# DC-DC_Converter_Module_V1_1.net
KiCad netlist of a schematic drawn in EAGLE
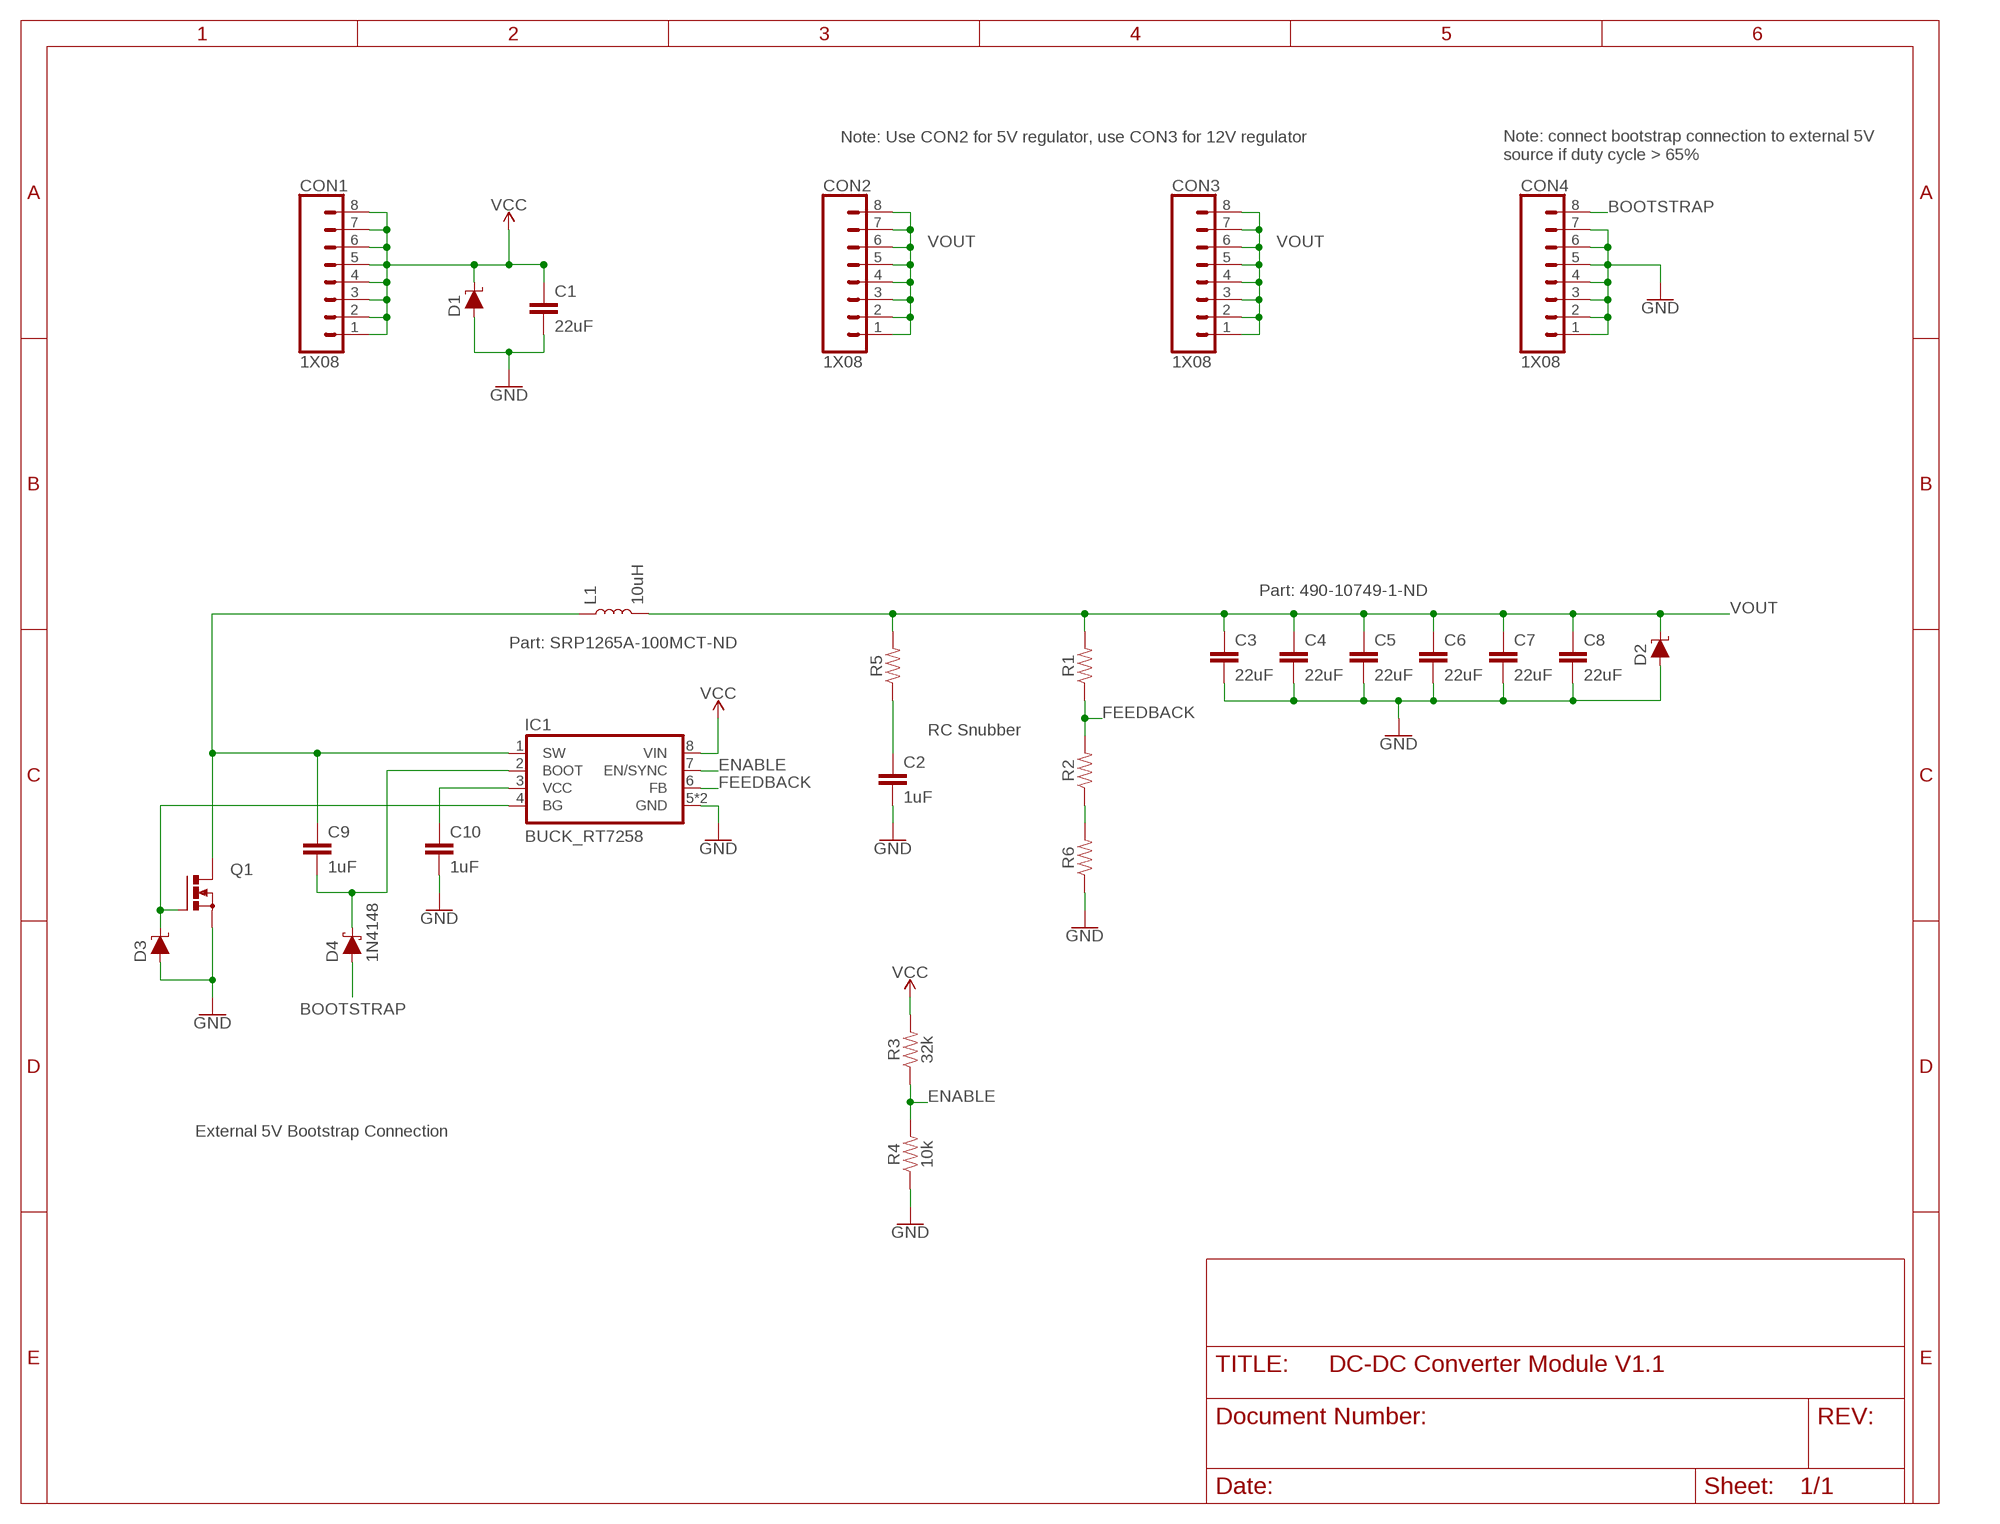
[diagram p0: schematic, sheet 1]

(export (version "E")
  (design (tool "Eeschema 10.0.6"))
  (components
    (comp (ref "C1")
      (value "22uF")
      (footprint "eagle-import:1210")
      (libsource (lib "eagle-import") (part "CAPACITOR_1210"))
    )
    (comp (ref "C2")
      (value "1uF")
      (footprint "eagle-import:0805")
      (libsource (lib "eagle-import") (part "CAPACITOR_0805"))
    )
    (comp (ref "C3")
      (value "22uF")
      (footprint "eagle-import:0805")
      (libsource (lib "eagle-import") (part "CAPACITOR_0805"))
    )
    (comp (ref "C4")
      (value "22uF")
      (footprint "eagle-import:0805")
      (libsource (lib "eagle-import") (part "CAPACITOR_0805"))
    )
    (comp (ref "C5")
      (value "22uF")
      (footprint "eagle-import:0805")
      (libsource (lib "eagle-import") (part "CAPACITOR_0805"))
    )
    (comp (ref "C6")
      (value "22uF")
      (footprint "eagle-import:0805")
      (libsource (lib "eagle-import") (part "CAPACITOR_0805"))
    )
    (comp (ref "C7")
      (value "22uF")
      (footprint "eagle-import:0805")
      (libsource (lib "eagle-import") (part "CAPACITOR_0805"))
    )
    (comp (ref "C8")
      (value "22uF")
      (footprint "eagle-import:0805")
      (libsource (lib "eagle-import") (part "CAPACITOR_0805"))
    )
    (comp (ref "C9")
      (value "1uF")
      (footprint "eagle-import:0805")
      (libsource (lib "eagle-import") (part "CAPACITOR_0805"))
    )
    (comp (ref "C10")
      (value "1uF")
      (footprint "eagle-import:0805")
      (libsource (lib "eagle-import") (part "CAPACITOR_0805"))
    )
    (comp (ref "CON1")
      (value "1X08")
      (footprint "eagle-import:1X08")
      (libsource (lib "eagle-import") (part "1X08"))
    )
    (comp (ref "CON2")
      (value "1X08")
      (footprint "eagle-import:1X08")
      (libsource (lib "eagle-import") (part "1X08"))
    )
    (comp (ref "CON3")
      (value "1X08")
      (footprint "eagle-import:1X08")
      (libsource (lib "eagle-import") (part "1X08"))
    )
    (comp (ref "CON4")
      (value "1X08")
      (footprint "eagle-import:1X08")
      (libsource (lib "eagle-import") (part "1X08"))
    )
    (comp (ref "D1")
      (value "DIODE_TVS_DO-214AA")
      (footprint "eagle-import:DO214AA")
      (libsource (lib "eagle-import") (part "DIODE_TVS_DO-214AA"))
    )
    (comp (ref "D2")
      (value "DIODE_TVS_DO-214AA")
      (footprint "eagle-import:DO214AA")
      (libsource (lib "eagle-import") (part "DIODE_TVS_DO-214AA"))
    )
    (comp (ref "D3")
      (value "DIODE_TVS_DO-214AA")
      (footprint "eagle-import:DO214AA")
      (libsource (lib "eagle-import") (part "DIODE_TVS_DO-214AA"))
    )
    (comp (ref "D4")
      (value "1N4148")
      (footprint "eagle-import:SOD123FL")
      (libsource (lib "eagle-import") (part "DIODE_SCHOTTKY_SOD123F"))
    )
    (comp (ref "IC1")
      (value "BUCK_RT7258")
      (footprint "eagle-import:SOP-8_HEATSINK")
      (libsource (lib "eagle-import") (part "BUCK_RT7258"))
    )
    (comp (ref "L1")
      (value "10uH")
      (footprint "eagle-import:INDUCTOR_BOURNS_SRP1265A")
      (libsource (lib "eagle-import") (part "INDUCTOR_BOURNS_SRP1265A"))
    )
    (comp (ref "Q1")
      (value "MOSFET_NMOS_TO-263")
      (footprint "eagle-import:TO-263_D2PAK")
      (libsource (lib "eagle-import") (part "MOSFET_NMOS_TO-263"))
    )
    (comp (ref "R1")
      (value "RESISTOR_0805")
      (footprint "eagle-import:0805")
      (libsource (lib "eagle-import") (part "RESISTOR_0805"))
    )
    (comp (ref "R2")
      (value "RESISTOR_0805")
      (footprint "eagle-import:0805")
      (libsource (lib "eagle-import") (part "RESISTOR_0805"))
    )
    (comp (ref "R3")
      (value "32k")
      (footprint "eagle-import:0805")
      (libsource (lib "eagle-import") (part "RESISTOR_0805"))
    )
    (comp (ref "R4")
      (value "10k")
      (footprint "eagle-import:0805")
      (libsource (lib "eagle-import") (part "RESISTOR_0805"))
    )
    (comp (ref "R5")
      (value "RESISTOR_0805")
      (footprint "eagle-import:0805")
      (libsource (lib "eagle-import") (part "RESISTOR_0805"))
    )
    (comp (ref "R6")
      (value "RESISTOR_0805")
      (footprint "eagle-import:0805")
      (libsource (lib "eagle-import") (part "RESISTOR_0805"))
    )
  )
  (nets
    (net (code "1") (name "/BOOTSTRAP") (class "Default")
      (node (ref "CON4") (pin "8") (pinfunction "8_8") (pintype "passive"))
      (node (ref "D4") (pin "A") (pinfunction "A_A") (pintype "passive"))
    )
    (net (code "2") (name "/ENABLE") (class "Default")
      (node (ref "IC1") (pin "7") (pinfunction "EN/SYNC_7") (pintype "bidirectional"))
      (node (ref "R3") (pin "1") (pinfunction "1_1") (pintype "passive"))
      (node (ref "R4") (pin "2") (pinfunction "2_2") (pintype "passive"))
    )
    (net (code "3") (name "/FEEDBACK") (class "Default")
      (node (ref "IC1") (pin "6") (pinfunction "FB_6") (pintype "bidirectional"))
      (node (ref "R1") (pin "1") (pinfunction "1_1") (pintype "passive"))
      (node (ref "R2") (pin "2") (pinfunction "2_2") (pintype "passive"))
    )
    (net (code "4") (name "/VOUT") (class "Default")
      (node (ref "C3") (pin "1") (pinfunction "1_1") (pintype "passive"))
      (node (ref "C4") (pin "1") (pinfunction "1_1") (pintype "passive"))
      (node (ref "C5") (pin "1") (pinfunction "1_1") (pintype "passive"))
      (node (ref "C6") (pin "1") (pinfunction "1_1") (pintype "passive"))
      (node (ref "C7") (pin "1") (pinfunction "1_1") (pintype "passive"))
      (node (ref "C8") (pin "1") (pinfunction "1_1") (pintype "passive"))
      (node (ref "CON2") (pin "1") (pinfunction "1_1") (pintype "passive"))
      (node (ref "CON2") (pin "2") (pinfunction "2_2") (pintype "passive"))
      (node (ref "CON2") (pin "3") (pinfunction "3_3") (pintype "passive"))
      (node (ref "CON2") (pin "4") (pinfunction "4_4") (pintype "passive"))
      (node (ref "CON2") (pin "5") (pinfunction "5_5") (pintype "passive"))
      (node (ref "CON2") (pin "6") (pinfunction "6_6") (pintype "passive"))
      (node (ref "CON2") (pin "7") (pinfunction "7_7") (pintype "passive"))
      (node (ref "CON2") (pin "8") (pinfunction "8_8") (pintype "passive"))
      (node (ref "CON3") (pin "1") (pinfunction "1_1") (pintype "passive"))
      (node (ref "CON3") (pin "2") (pinfunction "2_2") (pintype "passive"))
      (node (ref "CON3") (pin "3") (pinfunction "3_3") (pintype "passive"))
      (node (ref "CON3") (pin "4") (pinfunction "4_4") (pintype "passive"))
      (node (ref "CON3") (pin "5") (pinfunction "5_5") (pintype "passive"))
      (node (ref "CON3") (pin "6") (pinfunction "6_6") (pintype "passive"))
      (node (ref "CON3") (pin "7") (pinfunction "7_7") (pintype "passive"))
      (node (ref "CON3") (pin "8") (pinfunction "8_8") (pintype "passive"))
      (node (ref "D2") (pin "C") (pinfunction "C_C") (pintype "passive"))
      (node (ref "L1") (pin "2") (pinfunction "2_2") (pintype "passive"))
      (node (ref "R1") (pin "2") (pinfunction "2_2") (pintype "passive"))
      (node (ref "R5") (pin "2") (pinfunction "2_2") (pintype "passive"))
    )
    (net (code "5") (name "GND") (class "Default")
      (node (ref "C1") (pin "2") (pinfunction "2_2") (pintype "passive"))
      (node (ref "C10") (pin "2") (pinfunction "2_2") (pintype "passive"))
      (node (ref "C2") (pin "2") (pinfunction "2_2") (pintype "passive"))
      (node (ref "C3") (pin "2") (pinfunction "2_2") (pintype "passive"))
      (node (ref "C4") (pin "2") (pinfunction "2_2") (pintype "passive"))
      (node (ref "C5") (pin "2") (pinfunction "2_2") (pintype "passive"))
      (node (ref "C6") (pin "2") (pinfunction "2_2") (pintype "passive"))
      (node (ref "C7") (pin "2") (pinfunction "2_2") (pintype "passive"))
      (node (ref "C8") (pin "2") (pinfunction "2_2") (pintype "passive"))
      (node (ref "CON4") (pin "1") (pinfunction "1_1") (pintype "passive"))
      (node (ref "CON4") (pin "2") (pinfunction "2_2") (pintype "passive"))
      (node (ref "CON4") (pin "3") (pinfunction "3_3") (pintype "passive"))
      (node (ref "CON4") (pin "4") (pinfunction "4_4") (pintype "passive"))
      (node (ref "CON4") (pin "5") (pinfunction "5_5") (pintype "passive"))
      (node (ref "CON4") (pin "6") (pinfunction "6_6") (pintype "passive"))
      (node (ref "CON4") (pin "7") (pinfunction "7_7") (pintype "passive"))
      (node (ref "D1") (pin "A") (pinfunction "A_A") (pintype "passive"))
      (node (ref "D2") (pin "A") (pinfunction "A_A") (pintype "passive"))
      (node (ref "D3") (pin "A") (pinfunction "A_A") (pintype "passive"))
      (node (ref "IC1") (pin "5") (pinfunction "GND_5") (pintype "bidirectional"))
      (node (ref "IC1") (pin "GND") (pinfunction "GND_GND") (pintype "bidirectional"))
      (node (ref "Q1") (pin "3") (pinfunction "S_3") (pintype "passive"))
      (node (ref "R4") (pin "1") (pinfunction "1_1") (pintype "passive"))
      (node (ref "R6") (pin "1") (pinfunction "1_1") (pintype "passive"))
    )
    (net (code "6") (name "Net-(C2-Pad1)") (class "Default")
      (node (ref "C2") (pin "1") (pinfunction "1_1") (pintype "passive"))
      (node (ref "R5") (pin "1") (pinfunction "1_1") (pintype "passive"))
    )
    (net (code "7") (name "Net-(IC1-BG)") (class "Default")
      (node (ref "D3") (pin "C") (pinfunction "C_C") (pintype "passive"))
      (node (ref "IC1") (pin "4") (pinfunction "BG_4") (pintype "bidirectional"))
      (node (ref "Q1") (pin "1") (pinfunction "G_1") (pintype "passive"))
    )
    (net (code "8") (name "Net-(IC1-BOOT)") (class "Default")
      (node (ref "C9") (pin "2") (pinfunction "2_2") (pintype "passive"))
      (node (ref "D4") (pin "C") (pinfunction "C_C") (pintype "passive"))
      (node (ref "IC1") (pin "2") (pinfunction "BOOT_2") (pintype "bidirectional"))
    )
    (net (code "9") (name "Net-(IC1-SW)") (class "Default")
      (node (ref "C9") (pin "1") (pinfunction "1_1") (pintype "passive"))
      (node (ref "IC1") (pin "1") (pinfunction "SW_1") (pintype "bidirectional"))
      (node (ref "L1") (pin "1") (pinfunction "1_1") (pintype "passive"))
      (node (ref "Q1") (pin "2") (pinfunction "D_2") (pintype "passive"))
    )
    (net (code "10") (name "Net-(IC1-VCC)") (class "Default")
      (node (ref "C10") (pin "1") (pinfunction "1_1") (pintype "passive"))
      (node (ref "IC1") (pin "3") (pinfunction "VCC_3") (pintype "bidirectional"))
    )
    (net (code "11") (name "Net-(R2-Pad1)") (class "Default")
      (node (ref "R2") (pin "1") (pinfunction "1_1") (pintype "passive"))
      (node (ref "R6") (pin "2") (pinfunction "2_2") (pintype "passive"))
    )
    (net (code "12") (name "VCC") (class "Default")
      (node (ref "C1") (pin "1") (pinfunction "1_1") (pintype "passive"))
      (node (ref "CON1") (pin "1") (pinfunction "1_1") (pintype "passive"))
      (node (ref "CON1") (pin "2") (pinfunction "2_2") (pintype "passive"))
      (node (ref "CON1") (pin "3") (pinfunction "3_3") (pintype "passive"))
      (node (ref "CON1") (pin "4") (pinfunction "4_4") (pintype "passive"))
      (node (ref "CON1") (pin "5") (pinfunction "5_5") (pintype "passive"))
      (node (ref "CON1") (pin "6") (pinfunction "6_6") (pintype "passive"))
      (node (ref "CON1") (pin "7") (pinfunction "7_7") (pintype "passive"))
      (node (ref "CON1") (pin "8") (pinfunction "8_8") (pintype "passive"))
      (node (ref "D1") (pin "C") (pinfunction "C_C") (pintype "passive"))
      (node (ref "IC1") (pin "8") (pinfunction "VIN_8") (pintype "bidirectional"))
      (node (ref "R3") (pin "2") (pinfunction "2_2") (pintype "passive"))
    )
  )
)
